# tiny_buck.net
KiCad netlist of a schematic drawn in Altium Designer
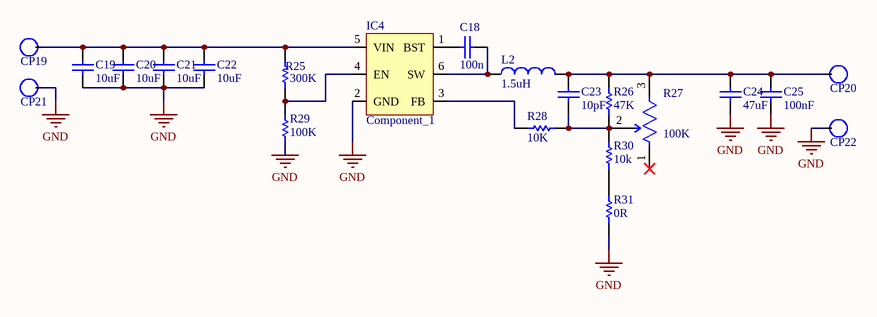
[diagram p0: tiny_buck.SchDoc]

(export (version "E")
  (design (tool "Eeschema 10.0.6"))
  (components
    (comp (ref "C18")
      (value "100n")
      (footprint "SMD-0603-RES")
      (description "Capacitor")
      (libsource (lib "Simulation Generic Components") (part "Capacitor"))
    )
    (comp (ref "C19")
      (value "10uF")
      (footprint "SMD-0603-RES")
      (description "Capacitor")
      (libsource (lib "Simulation Generic Components") (part "Capacitor"))
    )
    (comp (ref "C20")
      (value "10uF")
      (footprint "SMD-0603-RES")
      (description "Capacitor")
      (libsource (lib "Simulation Generic Components") (part "Capacitor"))
    )
    (comp (ref "C21")
      (value "10uF")
      (footprint "SMD-0603-RES")
      (description "Capacitor")
      (libsource (lib "Simulation Generic Components") (part "Capacitor"))
    )
    (comp (ref "C22")
      (value "10uF")
      (footprint "SMD-0603-RES")
      (description "Capacitor")
      (libsource (lib "Simulation Generic Components") (part "Capacitor"))
    )
    (comp (ref "C23")
      (value "10pF")
      (footprint "SMD-0603-RES")
      (description "Capacitor")
      (libsource (lib "Simulation Generic Components") (part "Capacitor"))
    )
    (comp (ref "C24")
      (value "47uF")
      (footprint "SMD-0805-RES")
      (description "Capacitor")
      (libsource (lib "Simulation Generic Components") (part "Capacitor"))
    )
    (comp (ref "C25")
      (value "100nF")
      (footprint "SMD-0603-RES")
      (description "Capacitor")
      (libsource (lib "Simulation Generic Components") (part "Capacitor"))
    )
    (comp (ref "CP19")
      (value "CONNECT_PAD")
      (footprint "ROUND_SMALL")
      (libsource (lib "solderpad") (part "CONNECT_PAD"))
    )
    (comp (ref "CP20")
      (value "CONNECT_PAD")
      (footprint "ROUND_SMALL")
      (libsource (lib "solderpad") (part "CONNECT_PAD"))
    )
    (comp (ref "CP21")
      (value "CONNECT_PAD")
      (footprint "ROUND_SMALL")
      (libsource (lib "solderpad") (part "CONNECT_PAD"))
    )
    (comp (ref "CP22")
      (value "CONNECT_PAD")
      (footprint "ROUND_SMALL")
      (libsource (lib "solderpad") (part "CONNECT_PAD"))
    )
    (comp (ref "IC4")
      (value "Component_1")
      (footprint "SOT95P280X130-6N")
      (libsource (lib "LP6450B6F") (part "Component_1"))
    )
    (comp (ref "L2")
      (value "1.5uH")
      (footprint "SMD-1206-RES")
      (description "Inductor")
      (fields (field (name "Comment") "Cybermax CMLO252010F1R5MTT"))
      (libsource (lib "Simulation Generic Components") (part "Inductor"))
    )
    (comp (ref "R25")
      (value "300K")
      (footprint "SMD-0603-RES")
      (description "Resistor")
      (libsource (lib "Simulation Generic Components") (part "Resistor"))
    )
    (comp (ref "R26")
      (value "47K")
      (footprint "SMD-0603-RES")
      (description "Resistor")
      (libsource (lib "Simulation Generic Components") (part "Resistor"))
    )
    (comp (ref "R27")
      (value "TC33X-2-104E")
      (footprint "FP-TC33X-2-MFG")
      (description "TRIMMER 100K OHM 0.1W J LEAD TOP")
      (fields (field (name "RESISTANCE") "100K") (field (name "TOLERANCE") "25%"))
      (libsource (lib "Altium Content Vault") (part "13357d81287629c2fd191d242cfa50c"))
    )
    (comp (ref "R28")
      (value "10K")
      (footprint "SMD-0603-RES")
      (description "Resistor")
      (libsource (lib "Simulation Generic Components") (part "Resistor"))
    )
    (comp (ref "R29")
      (value "100K")
      (footprint "SMD-0603-RES")
      (description "Resistor")
      (libsource (lib "Simulation Generic Components") (part "Resistor"))
    )
    (comp (ref "R30")
      (value "10k")
      (footprint "SMD-0603-RES")
      (description "Resistor")
      (libsource (lib "Simulation Generic Components") (part "Resistor"))
    )
    (comp (ref "R31")
      (value "0R")
      (footprint "SMD-0603-RES")
      (description "Resistor")
      (libsource (lib "Simulation Generic Components") (part "Resistor"))
    )
  )
  (nets
    (net (code "1") (name "GND") (class "Default")
      (node (ref "C19") (pin "1") (pinfunction "1_1") (pintype "passive"))
      (node (ref "C20") (pin "1") (pinfunction "1_1") (pintype "passive"))
      (node (ref "C21") (pin "1") (pinfunction "1_1") (pintype "passive"))
      (node (ref "C22") (pin "1") (pinfunction "1_1") (pintype "passive"))
      (node (ref "C24") (pin "1") (pinfunction "1_1") (pintype "passive"))
      (node (ref "C25") (pin "1") (pinfunction "1_1") (pintype "passive"))
      (node (ref "CP21") (pin "1") (pinfunction "1_1") (pintype "passive"))
      (node (ref "CP22") (pin "1") (pinfunction "1_1") (pintype "passive"))
      (node (ref "IC4") (pin "2") (pinfunction "GND_2") (pintype "passive"))
      (node (ref "R29") (pin "2") (pinfunction "2_2") (pintype "passive"))
      (node (ref "R31") (pin "1") (pinfunction "1_1") (pintype "passive"))
    )
    (net (code "2") (name "Net-(IC4-BST)") (class "Default")
      (node (ref "C18") (pin "2") (pinfunction "2_2") (pintype "passive"))
      (node (ref "IC4") (pin "1") (pinfunction "BST_1") (pintype "passive"))
    )
    (net (code "3") (name "Net-(IC4-EN)") (class "Default")
      (node (ref "IC4") (pin "4") (pinfunction "EN_4") (pintype "passive"))
      (node (ref "R25") (pin "1") (pinfunction "1_1") (pintype "passive"))
      (node (ref "R29") (pin "1") (pinfunction "1_1") (pintype "passive"))
    )
    (net (code "4") (name "Net-(IC4-FB)") (class "Default")
      (node (ref "IC4") (pin "3") (pinfunction "FB_3") (pintype "passive"))
      (node (ref "R28") (pin "2") (pinfunction "2_2") (pintype "passive"))
    )
    (net (code "5") (name "Net-(IC4-SW)") (class "Default")
      (node (ref "C18") (pin "1") (pinfunction "1_1") (pintype "passive"))
      (node (ref "IC4") (pin "6") (pinfunction "SW_6") (pintype "passive"))
      (node (ref "L2") (pin "1") (pinfunction "1_1") (pintype "passive"))
    )
    (net (code "6") (name "Net-(IC4-VIN)") (class "Default")
      (node (ref "C19") (pin "2") (pinfunction "2_2") (pintype "passive"))
      (node (ref "C20") (pin "2") (pinfunction "2_2") (pintype "passive"))
      (node (ref "C21") (pin "2") (pinfunction "2_2") (pintype "passive"))
      (node (ref "C22") (pin "2") (pinfunction "2_2") (pintype "passive"))
      (node (ref "CP19") (pin "1") (pinfunction "1_1") (pintype "passive"))
      (node (ref "IC4") (pin "5") (pinfunction "VIN_5") (pintype "passive"))
      (node (ref "R25") (pin "2") (pinfunction "2_2") (pintype "passive"))
    )
    (net (code "7") (name "Net-(R27-CW)") (class "Default")
      (node (ref "C23") (pin "2") (pinfunction "2_2") (pintype "passive"))
      (node (ref "C24") (pin "2") (pinfunction "2_2") (pintype "passive"))
      (node (ref "C25") (pin "2") (pinfunction "2_2") (pintype "passive"))
      (node (ref "CP20") (pin "1") (pinfunction "1_1") (pintype "passive"))
      (node (ref "L2") (pin "2") (pinfunction "2_2") (pintype "passive"))
      (node (ref "R26") (pin "2") (pinfunction "2_2") (pintype "passive"))
      (node (ref "R27") (pin "3") (pinfunction "CW_3") (pintype "passive"))
    )
    (net (code "8") (name "Net-(R27-WIPER)") (class "Default")
      (node (ref "C23") (pin "1") (pinfunction "1_1") (pintype "passive"))
      (node (ref "R26") (pin "1") (pinfunction "1_1") (pintype "passive"))
      (node (ref "R27") (pin "2") (pinfunction "WIPER_2") (pintype "passive"))
      (node (ref "R28") (pin "1") (pinfunction "1_1") (pintype "passive"))
      (node (ref "R30") (pin "2") (pinfunction "2_2") (pintype "passive"))
    )
    (net (code "9") (name "Net-(R30-Pad1)") (class "Default")
      (node (ref "R30") (pin "1") (pinfunction "1_1") (pintype "passive"))
      (node (ref "R31") (pin "2") (pinfunction "2_2") (pintype "passive"))
    )
    (net (code "10") (name "unconnected-(R27-CCW-Pad1)") (class "Default")
      (node (ref "R27") (pin "1") (pinfunction "CCW_1") (pintype "passive+no_connect"))
    )
  )
)
